# EE194_PCB.net
KiCad netlist of a schematic drawn in Altium Designer
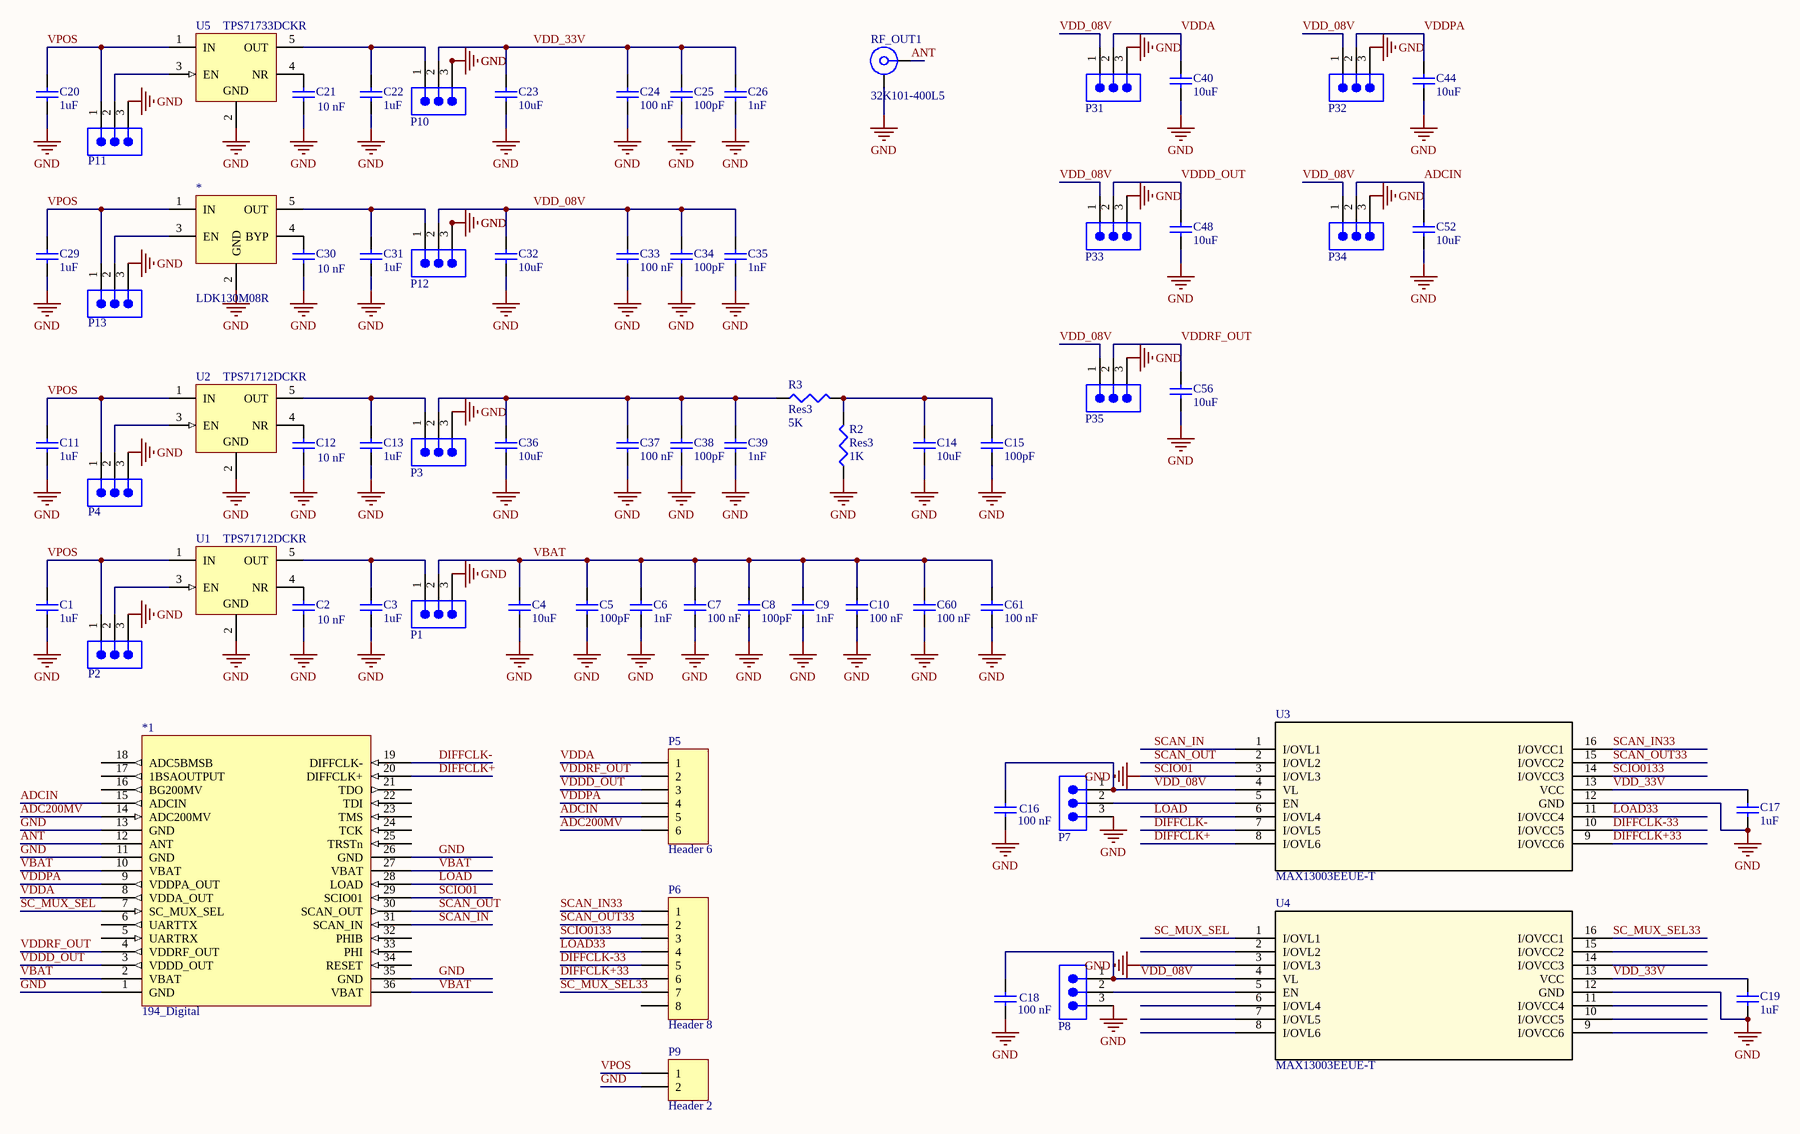
[diagram p0: EE194_PCB.SchDoc]

(export (version "E")
  (design (tool "Eeschema 10.0.6"))
  (components
    (comp (ref "*")
      (value "LDK130M08R")
      (footprint "SOT95P290X145-5N")
      (description "300 mA low quiescent current very low noise LDO (800mV)")
      (libsource (lib "EE194_PCB") (part "LDK130M08R"))
    )
    (comp (ref "*1")
      (value "194_Digital")
      (footprint "EE194_Analog_Chip")
      (libsource (lib "EE194_PCB") (part "194_Digital"))
    )
    (comp (ref "C1")
      (value "1uF")
      (footprint "CAPC0402(1005)60_M")
      (description "CAP 1uF 16V ±10% 0402 (1005 Metric) Thickness 0.6mm SMD")
      (fields (field (name "TOLERANCE") "Â±10%") (field (name "Comment") "CAP 1uF 16V 0402(1005)"))
      (libsource (lib "Altium Content Vault") (part "CAP"))
    )
    (comp (ref "C2")
      (value "GRM155R71H103KA88D")
      (footprint "CAPC1005X55X25LL05T10")
      (description "Chip Capacitor, 10 nF, +/- 10%, 50 V, -55 to 125 degC, 0402 (1005 Metric), RoHS, Tape and Reel")
      (fields
        (field (name "CAPACITANCE") "10 nF")
        (field (name "TOLERANCE") "10%")
        (field (name "MANUFACTURER") "Basic Passives")
      )
      (libsource (lib "Altium Content Vault") (part "CAP-NP-2"))
    )
    (comp (ref "C3")
      (value "1uF")
      (footprint "CAPC0402(1005)60_M")
      (description "CAP 1uF 16V ±10% 0402 (1005 Metric) Thickness 0.6mm SMD")
      (fields (field (name "TOLERANCE") "Â±10%") (field (name "Comment") "CAP 1uF 16V 0402(1005)"))
      (libsource (lib "Altium Content Vault") (part "CAP"))
    )
    (comp (ref "C4")
      (value "10uF")
      (footprint "CAPC0805(2012)145_N")
      (description "CAP 10uF 25V ±10% 0805 (2012 Metric) Thickness 1.45mm SMD")
      (fields (field (name "TOLERANCE") "Â±10%") (field (name "Comment") "CAP 10uF 25V 0805(2012)"))
      (libsource (lib "Altium Content Vault") (part "CAP"))
    )
    (comp (ref "C5")
      (value "100pF")
      (footprint "CAPC0402(1005)60_L")
      (description "CAP 100pF 16V ±1% 0402 (1005 Metric) Thickness 0.6mm SMD")
      (fields (field (name "TOLERANCE") "Â±1%") (field (name "Comment") "CAP 100pF 16V 0402(1005)"))
      (libsource (lib "Altium Content Vault") (part "CAP"))
    )
    (comp (ref "C6")
      (value "1nF")
      (footprint "CAPC0402(1005)60_L")
      (description "CAP 1nF 16V ±1% 0402 (1005 Metric) Thickness 0.6mm SMD")
      (fields (field (name "TOLERANCE") "Â±1%") (field (name "Comment") "CAP 1nF 16V 0402(1005)"))
      (libsource (lib "Altium Content Vault") (part "CAP"))
    )
    (comp (ref "C7")
      (value "0402ZD104KAT2A")
      (footprint "CAPC1005X56X25LL10T15")
      (description "Chip Capacitor, 0.1 uF, +/- 10%, 10 V, -55 to 85 degC, 0402 (1005 Metric), RoHS, Tape and Reel")
      (fields (field (name "CAPACITANCE") "100 nF") (field (name "TOLERANCE") "10%"))
      (libsource (lib "Altium Content Vault") (part "CAP-NP-2"))
    )
    (comp (ref "C8")
      (value "100pF")
      (footprint "CAPC0402(1005)60_L")
      (description "CAP 100pF 16V ±1% 0402 (1005 Metric) Thickness 0.6mm SMD")
      (fields (field (name "TOLERANCE") "Â±1%") (field (name "Comment") "CAP 100pF 16V 0402(1005)"))
      (libsource (lib "Altium Content Vault") (part "CAP"))
    )
    (comp (ref "C9")
      (value "1nF")
      (footprint "CAPC0402(1005)60_L")
      (description "CAP 1nF 16V ±1% 0402 (1005 Metric) Thickness 0.6mm SMD")
      (fields (field (name "TOLERANCE") "Â±1%") (field (name "Comment") "CAP 1nF 16V 0402(1005)"))
      (libsource (lib "Altium Content Vault") (part "CAP"))
    )
    (comp (ref "C10")
      (value "0402ZD104KAT2A")
      (footprint "CAPC1005X56X25LL10T15")
      (description "Chip Capacitor, 0.1 uF, +/- 10%, 10 V, -55 to 85 degC, 0402 (1005 Metric), RoHS, Tape and Reel")
      (fields (field (name "CAPACITANCE") "100 nF") (field (name "TOLERANCE") "10%"))
      (libsource (lib "Altium Content Vault") (part "CAP-NP-2"))
    )
    (comp (ref "C11")
      (value "1uF")
      (footprint "CAPC0402(1005)60_M")
      (description "CAP 1uF 16V ±10% 0402 (1005 Metric) Thickness 0.6mm SMD")
      (fields (field (name "TOLERANCE") "Â±10%") (field (name "Comment") "CAP 1uF 16V 0402(1005)"))
      (libsource (lib "Altium Content Vault") (part "CAP"))
    )
    (comp (ref "C12")
      (value "GRM155R71H103KA88D")
      (footprint "CAPC1005X55X25LL05T10")
      (description "Chip Capacitor, 10 nF, +/- 10%, 50 V, -55 to 125 degC, 0402 (1005 Metric), RoHS, Tape and Reel")
      (fields
        (field (name "CAPACITANCE") "10 nF")
        (field (name "TOLERANCE") "10%")
        (field (name "MANUFACTURER") "Basic Passives")
      )
      (libsource (lib "Altium Content Vault") (part "CAP-NP-2"))
    )
    (comp (ref "C13")
      (value "1uF")
      (footprint "CAPC0402(1005)60_M")
      (description "CAP 1uF 16V ±10% 0402 (1005 Metric) Thickness 0.6mm SMD")
      (fields (field (name "TOLERANCE") "Â±10%") (field (name "Comment") "CAP 1uF 16V 0402(1005)"))
      (libsource (lib "Altium Content Vault") (part "CAP"))
    )
    (comp (ref "C14")
      (value "10uF")
      (footprint "CAPC0805(2012)145_N")
      (description "CAP 10uF 25V ±10% 0805 (2012 Metric) Thickness 1.45mm SMD")
      (fields (field (name "TOLERANCE") "Â±10%") (field (name "Comment") "CAP 10uF 25V 0805(2012)"))
      (libsource (lib "Altium Content Vault") (part "CAP"))
    )
    (comp (ref "C15")
      (value "100pF")
      (footprint "CAPC0402(1005)60_L")
      (description "CAP 100pF 16V ±1% 0402 (1005 Metric) Thickness 0.6mm SMD")
      (fields (field (name "TOLERANCE") "Â±1%") (field (name "Comment") "CAP 100pF 16V 0402(1005)"))
      (libsource (lib "Altium Content Vault") (part "CAP"))
    )
    (comp (ref "C16")
      (value "0402ZD104KAT2A")
      (footprint "CAPC1005X56X25LL10T15")
      (description "Chip Capacitor, 0.1 uF, +/- 10%, 10 V, -55 to 85 degC, 0402 (1005 Metric), RoHS, Tape and Reel")
      (fields (field (name "CAPACITANCE") "100 nF") (field (name "TOLERANCE") "10%"))
      (libsource (lib "Altium Content Vault") (part "CAP-NP-2"))
    )
    (comp (ref "C17")
      (value "1uF")
      (footprint "CAPC0402(1005)60_M")
      (description "CAP 1uF 16V ±10% 0402 (1005 Metric) Thickness 0.6mm SMD")
      (fields (field (name "TOLERANCE") "Â±10%") (field (name "Comment") "CAP 1uF 16V 0402(1005)"))
      (libsource (lib "Altium Content Vault") (part "CAP"))
    )
    (comp (ref "C18")
      (value "0402ZD104KAT2A")
      (footprint "CAPC1005X56X25LL10T15")
      (description "Chip Capacitor, 0.1 uF, +/- 10%, 10 V, -55 to 85 degC, 0402 (1005 Metric), RoHS, Tape and Reel")
      (fields (field (name "CAPACITANCE") "100 nF") (field (name "TOLERANCE") "10%"))
      (libsource (lib "Altium Content Vault") (part "CAP-NP-2"))
    )
    (comp (ref "C19")
      (value "1uF")
      (footprint "CAPC0402(1005)60_M")
      (description "CAP 1uF 16V ±10% 0402 (1005 Metric) Thickness 0.6mm SMD")
      (fields (field (name "TOLERANCE") "Â±10%") (field (name "Comment") "CAP 1uF 16V 0402(1005)"))
      (libsource (lib "Altium Content Vault") (part "CAP"))
    )
    (comp (ref "C20")
      (value "1uF")
      (footprint "CAPC0402(1005)60_M")
      (description "CAP 1uF 16V ±10% 0402 (1005 Metric) Thickness 0.6mm SMD")
      (fields (field (name "TOLERANCE") "Â±10%") (field (name "Comment") "CAP 1uF 16V 0402(1005)"))
      (libsource (lib "Altium Content Vault") (part "CAP"))
    )
    (comp (ref "C21")
      (value "GRM155R71H103KA88D")
      (footprint "CAPC1005X55X25LL05T10")
      (description "Chip Capacitor, 10 nF, +/- 10%, 50 V, -55 to 125 degC, 0402 (1005 Metric), RoHS, Tape and Reel")
      (fields
        (field (name "CAPACITANCE") "10 nF")
        (field (name "TOLERANCE") "10%")
        (field (name "MANUFACTURER") "Basic Passives")
      )
      (libsource (lib "Altium Content Vault") (part "CAP-NP-2"))
    )
    (comp (ref "C22")
      (value "1uF")
      (footprint "CAPC0402(1005)60_M")
      (description "CAP 1uF 16V ±10% 0402 (1005 Metric) Thickness 0.6mm SMD")
      (fields (field (name "TOLERANCE") "Â±10%") (field (name "Comment") "CAP 1uF 16V 0402(1005)"))
      (libsource (lib "Altium Content Vault") (part "CAP"))
    )
    (comp (ref "C23")
      (value "10uF")
      (footprint "CAPC0805(2012)145_N")
      (description "CAP 10uF 25V ±10% 0805 (2012 Metric) Thickness 1.45mm SMD")
      (fields (field (name "TOLERANCE") "Â±10%") (field (name "Comment") "CAP 10uF 25V 0805(2012)"))
      (libsource (lib "Altium Content Vault") (part "CAP"))
    )
    (comp (ref "C24")
      (value "0402ZD104KAT2A")
      (footprint "CAPC1005X56X25LL10T15")
      (description "Chip Capacitor, 0.1 uF, +/- 10%, 10 V, -55 to 85 degC, 0402 (1005 Metric), RoHS, Tape and Reel")
      (fields (field (name "CAPACITANCE") "100 nF") (field (name "TOLERANCE") "10%"))
      (libsource (lib "Altium Content Vault") (part "CAP-NP-2"))
    )
    (comp (ref "C25")
      (value "100pF")
      (footprint "CAPC0402(1005)60_L")
      (description "CAP 100pF 16V ±1% 0402 (1005 Metric) Thickness 0.6mm SMD")
      (fields (field (name "TOLERANCE") "Â±1%") (field (name "Comment") "CAP 100pF 16V 0402(1005)"))
      (libsource (lib "Altium Content Vault") (part "CAP"))
    )
    (comp (ref "C26")
      (value "1nF")
      (footprint "CAPC0402(1005)60_L")
      (description "CAP 1nF 16V ±1% 0402 (1005 Metric) Thickness 0.6mm SMD")
      (fields (field (name "TOLERANCE") "Â±1%") (field (name "Comment") "CAP 1nF 16V 0402(1005)"))
      (libsource (lib "Altium Content Vault") (part "CAP"))
    )
    (comp (ref "C29")
      (value "1uF")
      (footprint "CAPC0402(1005)60_M")
      (description "CAP 1uF 16V ±10% 0402 (1005 Metric) Thickness 0.6mm SMD")
      (fields (field (name "TOLERANCE") "Â±10%") (field (name "Comment") "CAP 1uF 16V 0402(1005)"))
      (libsource (lib "Altium Content Vault") (part "CAP"))
    )
    (comp (ref "C30")
      (value "GRM155R71H103KA88D")
      (footprint "CAPC1005X55X25LL05T10")
      (description "Chip Capacitor, 10 nF, +/- 10%, 50 V, -55 to 125 degC, 0402 (1005 Metric), RoHS, Tape and Reel")
      (fields
        (field (name "CAPACITANCE") "10 nF")
        (field (name "TOLERANCE") "10%")
        (field (name "MANUFACTURER") "Basic Passives")
      )
      (libsource (lib "Altium Content Vault") (part "CAP-NP-2"))
    )
    (comp (ref "C31")
      (value "1uF")
      (footprint "CAPC0402(1005)60_M")
      (description "CAP 1uF 16V ±10% 0402 (1005 Metric) Thickness 0.6mm SMD")
      (fields (field (name "TOLERANCE") "Â±10%") (field (name "Comment") "CAP 1uF 16V 0402(1005)"))
      (libsource (lib "Altium Content Vault") (part "CAP"))
    )
    (comp (ref "C32")
      (value "10uF")
      (footprint "CAPC0805(2012)145_N")
      (description "CAP 10uF 25V ±10% 0805 (2012 Metric) Thickness 1.45mm SMD")
      (fields (field (name "TOLERANCE") "Â±10%") (field (name "Comment") "CAP 10uF 25V 0805(2012)"))
      (libsource (lib "Altium Content Vault") (part "CAP"))
    )
    (comp (ref "C33")
      (value "0402ZD104KAT2A")
      (footprint "CAPC1005X56X25LL10T15")
      (description "Chip Capacitor, 0.1 uF, +/- 10%, 10 V, -55 to 85 degC, 0402 (1005 Metric), RoHS, Tape and Reel")
      (fields (field (name "CAPACITANCE") "100 nF") (field (name "TOLERANCE") "10%"))
      (libsource (lib "Altium Content Vault") (part "CAP-NP-2"))
    )
    (comp (ref "C34")
      (value "100pF")
      (footprint "CAPC0402(1005)60_L")
      (description "CAP 100pF 16V ±1% 0402 (1005 Metric) Thickness 0.6mm SMD")
      (fields (field (name "TOLERANCE") "Â±1%") (field (name "Comment") "CAP 100pF 16V 0402(1005)"))
      (libsource (lib "Altium Content Vault") (part "CAP"))
    )
    (comp (ref "C35")
      (value "1nF")
      (footprint "CAPC0402(1005)60_L")
      (description "CAP 1nF 16V ±1% 0402 (1005 Metric) Thickness 0.6mm SMD")
      (fields (field (name "TOLERANCE") "Â±1%") (field (name "Comment") "CAP 1nF 16V 0402(1005)"))
      (libsource (lib "Altium Content Vault") (part "CAP"))
    )
    (comp (ref "C36")
      (value "10uF")
      (footprint "CAPC0805(2012)145_N")
      (description "CAP 10uF 25V ±10% 0805 (2012 Metric) Thickness 1.45mm SMD")
      (fields (field (name "TOLERANCE") "Â±10%") (field (name "Comment") "CAP 10uF 25V 0805(2012)"))
      (libsource (lib "Altium Content Vault") (part "CAP"))
    )
    (comp (ref "C37")
      (value "0402ZD104KAT2A")
      (footprint "CAPC1005X56X25LL10T15")
      (description "Chip Capacitor, 0.1 uF, +/- 10%, 10 V, -55 to 85 degC, 0402 (1005 Metric), RoHS, Tape and Reel")
      (fields (field (name "CAPACITANCE") "100 nF") (field (name "TOLERANCE") "10%"))
      (libsource (lib "Altium Content Vault") (part "CAP-NP-2"))
    )
    (comp (ref "C38")
      (value "100pF")
      (footprint "CAPC0402(1005)60_L")
      (description "CAP 100pF 16V ±1% 0402 (1005 Metric) Thickness 0.6mm SMD")
      (fields (field (name "TOLERANCE") "Â±1%") (field (name "Comment") "CAP 100pF 16V 0402(1005)"))
      (libsource (lib "Altium Content Vault") (part "CAP"))
    )
    (comp (ref "C39")
      (value "1nF")
      (footprint "CAPC0402(1005)60_L")
      (description "CAP 1nF 16V ±1% 0402 (1005 Metric) Thickness 0.6mm SMD")
      (fields (field (name "TOLERANCE") "Â±1%") (field (name "Comment") "CAP 1nF 16V 0402(1005)"))
      (libsource (lib "Altium Content Vault") (part "CAP"))
    )
    (comp (ref "C40")
      (value "10uF")
      (footprint "CAPC0805(2012)145_N")
      (description "CAP 10uF 25V ±10% 0805 (2012 Metric) Thickness 1.45mm SMD")
      (fields (field (name "TOLERANCE") "Â±10%") (field (name "Comment") "CAP 10uF 25V 0805(2012)"))
      (libsource (lib "Altium Content Vault") (part "CAP"))
    )
    (comp (ref "C44")
      (value "10uF")
      (footprint "CAPC0805(2012)145_N")
      (description "CAP 10uF 25V ±10% 0805 (2012 Metric) Thickness 1.45mm SMD")
      (fields (field (name "TOLERANCE") "Â±10%") (field (name "Comment") "CAP 10uF 25V 0805(2012)"))
      (libsource (lib "Altium Content Vault") (part "CAP"))
    )
    (comp (ref "C48")
      (value "10uF")
      (footprint "CAPC0805(2012)145_N")
      (description "CAP 10uF 25V ±10% 0805 (2012 Metric) Thickness 1.45mm SMD")
      (fields (field (name "TOLERANCE") "Â±10%") (field (name "Comment") "CAP 10uF 25V 0805(2012)"))
      (libsource (lib "Altium Content Vault") (part "CAP"))
    )
    (comp (ref "C52")
      (value "10uF")
      (footprint "CAPC0805(2012)145_N")
      (description "CAP 10uF 25V ±10% 0805 (2012 Metric) Thickness 1.45mm SMD")
      (fields (field (name "TOLERANCE") "Â±10%") (field (name "Comment") "CAP 10uF 25V 0805(2012)"))
      (libsource (lib "Altium Content Vault") (part "CAP"))
    )
    (comp (ref "C56")
      (value "10uF")
      (footprint "CAPC0805(2012)145_N")
      (description "CAP 10uF 25V ±10% 0805 (2012 Metric) Thickness 1.45mm SMD")
      (fields (field (name "TOLERANCE") "Â±10%") (field (name "Comment") "CAP 10uF 25V 0805(2012)"))
      (libsource (lib "Altium Content Vault") (part "CAP"))
    )
    (comp (ref "C60")
      (value "0402ZD104KAT2A")
      (footprint "CAPC1005X56X25LL10T15")
      (description "Chip Capacitor, 0.1 uF, +/- 10%, 10 V, -55 to 85 degC, 0402 (1005 Metric), RoHS, Tape and Reel")
      (fields (field (name "CAPACITANCE") "100 nF") (field (name "TOLERANCE") "10%"))
      (libsource (lib "EE194_PCB") (part "CAP-NP-2"))
    )
    (comp (ref "C61")
      (value "0402ZD104KAT2A")
      (footprint "CAPC0402(1005)60_L")
      (description "Chip Capacitor, 0.1 uF, +/- 10%, 10 V, -55 to 85 degC, 0402 (1005 Metric), RoHS, Tape and Reel")
      (fields (field (name "CAPACITANCE") "100 nF") (field (name "TOLERANCE") "10%"))
      (libsource (lib "EE194_PCB") (part "CAP-NP-2"))
    )
    (comp (ref "P1")
      (value "TSW-103-07-F-S")
      (footprint "SMTC-TSW-103-07-X-S")
      (description "0.025\" SQ Post Header, Through-hole, Vertical, -55 to 125 degC, 2.54 mm Pitch, 3-Pin, Male, RoHS")
      (fields (field (name "MANUFACTURER") "Samtec"))
      (libsource (lib "Altium Content Vault") (part "SMTC-TSW-103-X-X-S-X"))
    )
    (comp (ref "P2")
      (value "TSW-103-07-F-S")
      (footprint "SMTC-TSW-103-07-X-S")
      (description "0.025\" SQ Post Header, Through-hole, Vertical, -55 to 125 degC, 2.54 mm Pitch, 3-Pin, Male, RoHS")
      (fields (field (name "MANUFACTURER") "Samtec"))
      (libsource (lib "Altium Content Vault") (part "SMTC-TSW-103-X-X-S-X"))
    )
    (comp (ref "P3")
      (value "TSW-103-07-F-S")
      (footprint "SMTC-TSW-103-07-X-S")
      (description "0.025\" SQ Post Header, Through-hole, Vertical, -55 to 125 degC, 2.54 mm Pitch, 3-Pin, Male, RoHS")
      (fields (field (name "MANUFACTURER") "Samtec"))
      (libsource (lib "Altium Content Vault") (part "SMTC-TSW-103-X-X-S-X"))
    )
    (comp (ref "P4")
      (value "TSW-103-07-F-S")
      (footprint "SMTC-TSW-103-07-X-S")
      (description "0.025\" SQ Post Header, Through-hole, Vertical, -55 to 125 degC, 2.54 mm Pitch, 3-Pin, Male, RoHS")
      (fields (field (name "MANUFACTURER") "Samtec"))
      (libsource (lib "Altium Content Vault") (part "SMTC-TSW-103-X-X-S-X"))
    )
    (comp (ref "P5")
      (value "Header 6")
      (footprint "HDR1X6")
      (description "Header, 6-Pin")
      (fields (field (name "PUBLISHER") "Altium Limited"))
      (libsource (lib "Miscellaneous Connectors") (part "Header 6"))
    )
    (comp (ref "P6")
      (value "Header 8")
      (footprint "HDR1X8")
      (description "Header, 8-Pin")
      (fields (field (name "PUBLISHER") "Altium Limited"))
      (libsource (lib "Miscellaneous Connectors") (part "Header 8"))
    )
    (comp (ref "P7")
      (value "TSW-103-07-F-S")
      (footprint "SMTC-TSW-103-07-X-S")
      (description "0.025\" SQ Post Header, Through-hole, Vertical, -55 to 125 degC, 2.54 mm Pitch, 3-Pin, Male, RoHS")
      (fields (field (name "MANUFACTURER") "Samtec"))
      (libsource (lib "Altium Content Vault") (part "SMTC-TSW-103-X-X-S-X"))
    )
    (comp (ref "P8")
      (value "TSW-103-07-F-S")
      (footprint "SMTC-TSW-103-07-X-S")
      (description "0.025\" SQ Post Header, Through-hole, Vertical, -55 to 125 degC, 2.54 mm Pitch, 3-Pin, Male, RoHS")
      (fields (field (name "MANUFACTURER") "Samtec"))
      (libsource (lib "Altium Content Vault") (part "SMTC-TSW-103-X-X-S-X"))
    )
    (comp (ref "P9")
      (value "Header 2")
      (footprint "HDR1X2")
      (description "Header, 2-Pin")
      (fields (field (name "PUBLISHER") "Altium Limited"))
      (libsource (lib "Miscellaneous Connectors") (part "Header 2"))
    )
    (comp (ref "P10")
      (value "TSW-103-07-F-S")
      (footprint "SMTC-TSW-103-07-X-S")
      (description "0.025\" SQ Post Header, Through-hole, Vertical, -55 to 125 degC, 2.54 mm Pitch, 3-Pin, Male, RoHS")
      (fields (field (name "MANUFACTURER") "Samtec"))
      (libsource (lib "Altium Content Vault") (part "SMTC-TSW-103-X-X-S-X"))
    )
    (comp (ref "P11")
      (value "TSW-103-07-F-S")
      (footprint "SMTC-TSW-103-07-X-S")
      (description "0.025\" SQ Post Header, Through-hole, Vertical, -55 to 125 degC, 2.54 mm Pitch, 3-Pin, Male, RoHS")
      (fields (field (name "MANUFACTURER") "Samtec"))
      (libsource (lib "Altium Content Vault") (part "SMTC-TSW-103-X-X-S-X"))
    )
    (comp (ref "P12")
      (value "TSW-103-07-F-S")
      (footprint "SMTC-TSW-103-07-X-S")
      (description "0.025\" SQ Post Header, Through-hole, Vertical, -55 to 125 degC, 2.54 mm Pitch, 3-Pin, Male, RoHS")
      (fields (field (name "MANUFACTURER") "Samtec"))
      (libsource (lib "Altium Content Vault") (part "SMTC-TSW-103-X-X-S-X"))
    )
    (comp (ref "P13")
      (value "TSW-103-07-F-S")
      (footprint "SMTC-TSW-103-07-X-S")
      (description "0.025\" SQ Post Header, Through-hole, Vertical, -55 to 125 degC, 2.54 mm Pitch, 3-Pin, Male, RoHS")
      (fields (field (name "MANUFACTURER") "Samtec"))
      (libsource (lib "Altium Content Vault") (part "SMTC-TSW-103-X-X-S-X"))
    )
    (comp (ref "P31")
      (value "TSW-103-07-F-S")
      (footprint "SMTC-TSW-103-07-X-S")
      (description "0.025\" SQ Post Header, Through-hole, Vertical, -55 to 125 degC, 2.54 mm Pitch, 3-Pin, Male, RoHS")
      (fields (field (name "MANUFACTURER") "Samtec"))
      (libsource (lib "Altium Content Vault") (part "SMTC-TSW-103-X-X-S-X"))
    )
    (comp (ref "P32")
      (value "TSW-103-07-F-S")
      (footprint "SMTC-TSW-103-07-X-S")
      (description "0.025\" SQ Post Header, Through-hole, Vertical, -55 to 125 degC, 2.54 mm Pitch, 3-Pin, Male, RoHS")
      (fields (field (name "MANUFACTURER") "Samtec"))
      (libsource (lib "Altium Content Vault") (part "SMTC-TSW-103-X-X-S-X"))
    )
    (comp (ref "P33")
      (value "TSW-103-07-F-S")
      (footprint "SMTC-TSW-103-07-X-S")
      (description "0.025\" SQ Post Header, Through-hole, Vertical, -55 to 125 degC, 2.54 mm Pitch, 3-Pin, Male, RoHS")
      (fields (field (name "MANUFACTURER") "Samtec"))
      (libsource (lib "Altium Content Vault") (part "SMTC-TSW-103-X-X-S-X"))
    )
    (comp (ref "P34")
      (value "TSW-103-07-F-S")
      (footprint "SMTC-TSW-103-07-X-S")
      (description "0.025\" SQ Post Header, Through-hole, Vertical, -55 to 125 degC, 2.54 mm Pitch, 3-Pin, Male, RoHS")
      (fields (field (name "MANUFACTURER") "Samtec"))
      (libsource (lib "Altium Content Vault") (part "SMTC-TSW-103-X-X-S-X"))
    )
    (comp (ref "P35")
      (value "TSW-103-07-F-S")
      (footprint "SMTC-TSW-103-07-X-S")
      (description "0.025\" SQ Post Header, Through-hole, Vertical, -55 to 125 degC, 2.54 mm Pitch, 3-Pin, Male, RoHS")
      (fields (field (name "MANUFACTURER") "Samtec"))
      (libsource (lib "Altium Content Vault") (part "SMTC-TSW-103-X-X-S-X"))
    )
    (comp (ref "R2")
      (value "Res3")
      (footprint "J1-0603")
      (description "Resistor")
      (fields (field (name "ALTIUM_VALUE") "1K") (field (name "PUBLISHER") "Altium Limited"))
      (libsource (lib "Miscellaneous Devices") (part "Res3"))
    )
    (comp (ref "R3")
      (value "Res3")
      (footprint "J1-0603")
      (description "Resistor")
      (fields (field (name "ALTIUM_VALUE") "5K") (field (name "PUBLISHER") "Altium Limited"))
      (libsource (lib "Miscellaneous Devices") (part "Res3"))
    )
    (comp (ref "RF_OUT1")
      (value "32K101-400L5")
      (footprint "ROS-32K101-400L5_V")
      (description "SMA Straight Jack, Up to 18 GHz, -55 to 155 degC")
      (fields (field (name "MANUFACTURER") "Rosenberger"))
      (libsource (lib "Altium Content Vault") (part "ROS-CN-1F-RF1"))
    )
    (comp (ref "U1")
      (value "TPS71712DCKR")
      (footprint "DCK0005A_L")
      (fields (field (name "MANUFACTURER") "Texas Instruments"))
      (libsource (lib "Altium Content Vault") (part "TI-TPS79NXX-YYSOT5"))
    )
    (comp (ref "U2")
      (value "TPS71712DCKR")
      (footprint "DCK0005A_L")
      (fields (field (name "MANUFACTURER") "Texas Instruments"))
      (libsource (lib "Altium Content Vault") (part "TI-TPS79NXX-YYSOT5"))
    )
    (comp (ref "U3")
      (value "MAX13003EEUE-T")
      (footprint "21-0066J_16")
      (description "Imported")
      (libsource (lib "MAX13003") (part "MAX13003EEUE-T"))
    )
    (comp (ref "U4")
      (value "MAX13003EEUE-T")
      (footprint "21-0066J_16")
      (description "Imported")
      (libsource (lib "MAX13003") (part "MAX13003EEUE-T"))
    )
    (comp (ref "U5")
      (value "TPS71733DCKR")
      (footprint "DCK0005A_L")
      (fields (field (name "PARTNUMBER") "TPS71712DCKR") (field (name "MANUFACTURER") "Texas Instruments"))
      (libsource (lib "Altium Content Vault") (part "TI-TPS79NXX-YYSOT5"))
    )
  )
  (nets
    (net (code "1") (name "/ADC200MV") (class "Default")
      (node (ref "*1") (pin "14") (pinfunction "ADC200MV_14") (pintype "input"))
      (node (ref "P5") (pin "6") (pinfunction "6_6") (pintype "passive"))
    )
    (net (code "2") (name "/ADCIN") (class "Default")
      (node (ref "*1") (pin "15") (pinfunction "ADCIN_15") (pintype "output"))
      (node (ref "C52") (pin "2") (pinfunction "2_2") (pintype "passive"))
      (node (ref "P34") (pin "2") (pinfunction "2_2") (pintype "passive"))
      (node (ref "P5") (pin "5") (pinfunction "5_5") (pintype "passive"))
    )
    (net (code "3") (name "/ANT") (class "Default")
      (node (ref "*1") (pin "12") (pinfunction "ANT_12") (pintype "passive"))
      (node (ref "RF_OUT1") (pin "1") (pinfunction "1_1") (pintype "passive"))
    )
    (net (code "4") (name "/DIFFCLK+") (class "Default")
      (node (ref "*1") (pin "20") (pinfunction "DIFFCLK+_20") (pintype "input"))
      (node (ref "U3") (pin "8") (pinfunction "I/OVL6_8") (pintype "passive"))
    )
    (net (code "5") (name "/DIFFCLK+33") (class "Default")
      (node (ref "P6") (pin "6") (pinfunction "6_6") (pintype "passive"))
      (node (ref "U3") (pin "9") (pinfunction "I/OVCC6_9") (pintype "passive"))
    )
    (net (code "6") (name "/DIFFCLK-") (class "Default")
      (node (ref "*1") (pin "19") (pinfunction "DIFFCLK-_19") (pintype "input"))
      (node (ref "U3") (pin "7") (pinfunction "I/OVL5_7") (pintype "passive"))
    )
    (net (code "7") (name "/DIFFCLK-33") (class "Default")
      (node (ref "P6") (pin "5") (pinfunction "5_5") (pintype "passive"))
      (node (ref "U3") (pin "10") (pinfunction "I/OVCC5_10") (pintype "passive"))
    )
    (net (code "8") (name "/LOAD") (class "Default")
      (node (ref "*1") (pin "28") (pinfunction "LOAD_28") (pintype "input"))
      (node (ref "U3") (pin "6") (pinfunction "I/OVL4_6") (pintype "passive"))
    )
    (net (code "9") (name "/LOAD33") (class "Default")
      (node (ref "P6") (pin "4") (pinfunction "4_4") (pintype "passive"))
      (node (ref "U3") (pin "11") (pinfunction "I/OVCC4_11") (pintype "passive"))
    )
    (net (code "10") (name "/SCAN_IN") (class "Default")
      (node (ref "*1") (pin "31") (pinfunction "SCAN_IN_31") (pintype "input"))
      (node (ref "U3") (pin "1") (pinfunction "I/OVL1_1") (pintype "passive"))
    )
    (net (code "11") (name "/SCAN_IN33") (class "Default")
      (node (ref "P6") (pin "1") (pinfunction "1_1") (pintype "passive"))
      (node (ref "U3") (pin "16") (pinfunction "I/OVCC1_16") (pintype "passive"))
    )
    (net (code "12") (name "/SCAN_OUT") (class "Default")
      (node (ref "*1") (pin "30") (pinfunction "SCAN_OUT_30") (pintype "output"))
      (node (ref "U3") (pin "2") (pinfunction "I/OVL2_2") (pintype "passive"))
    )
    (net (code "13") (name "/SCAN_OUT33") (class "Default")
      (node (ref "P6") (pin "2") (pinfunction "2_2") (pintype "passive"))
      (node (ref "U3") (pin "15") (pinfunction "I/OVCC2_15") (pintype "passive"))
    )
    (net (code "14") (name "/SCIO0133") (class "Default")
      (node (ref "P6") (pin "3") (pinfunction "3_3") (pintype "passive"))
      (node (ref "U3") (pin "14") (pinfunction "I/OVCC3_14") (pintype "passive"))
    )
    (net (code "15") (name "/SC_MUX_SEL") (class "Default")
      (node (ref "*1") (pin "7") (pinfunction "SC_MUX_SEL_7") (pintype "input"))
      (node (ref "U4") (pin "1") (pinfunction "I/OVL1_1") (pintype "passive"))
    )
    (net (code "16") (name "/SC_MUX_SEL33") (class "Default")
      (node (ref "P6") (pin "7") (pinfunction "7_7") (pintype "passive"))
      (node (ref "U4") (pin "16") (pinfunction "I/OVCC1_16") (pintype "passive"))
    )
    (net (code "17") (name "/VBAT") (class "Default")
      (node (ref "*1") (pin "10") (pinfunction "VBAT_10") (pintype "power_in"))
      (node (ref "*1") (pin "2") (pinfunction "VBAT_2") (pintype "power_in"))
      (node (ref "*1") (pin "27") (pinfunction "VBAT_27") (pintype "power_in"))
      (node (ref "*1") (pin "36") (pinfunction "VBAT_36") (pintype "power_in"))
      (node (ref "C10") (pin "2") (pinfunction "2_2") (pintype "passive"))
      (node (ref "C4") (pin "2") (pinfunction "2_2") (pintype "passive"))
      (node (ref "C5") (pin "2") (pinfunction "2_2") (pintype "passive"))
      (node (ref "C6") (pin "2") (pinfunction "2_2") (pintype "passive"))
      (node (ref "C60") (pin "2") (pinfunction "2_2") (pintype "passive"))
      (node (ref "C61") (pin "2") (pinfunction "2_2") (pintype "passive"))
      (node (ref "C7") (pin "2") (pinfunction "2_2") (pintype "passive"))
      (node (ref "C8") (pin "2") (pinfunction "2_2") (pintype "passive"))
      (node (ref "C9") (pin "2") (pinfunction "2_2") (pintype "passive"))
      (node (ref "P1") (pin "2") (pinfunction "2_2") (pintype "passive"))
    )
    (net (code "18") (name "/VDDA") (class "Default")
      (node (ref "*1") (pin "8") (pinfunction "VDDA_OUT_8") (pintype "output"))
      (node (ref "C40") (pin "2") (pinfunction "2_2") (pintype "passive"))
      (node (ref "P31") (pin "2") (pinfunction "2_2") (pintype "passive"))
      (node (ref "P5") (pin "1") (pinfunction "1_1") (pintype "passive"))
    )
    (net (code "19") (name "/VDDD_OUT") (class "Default")
      (node (ref "*1") (pin "3") (pinfunction "VDDD_OUT_3") (pintype "output"))
      (node (ref "C48") (pin "2") (pinfunction "2_2") (pintype "passive"))
      (node (ref "P33") (pin "2") (pinfunction "2_2") (pintype "passive"))
      (node (ref "P5") (pin "3") (pinfunction "3_3") (pintype "passive"))
    )
    (net (code "20") (name "/VDDPA") (class "Default")
      (node (ref "*1") (pin "9") (pinfunction "VDDPA_OUT_9") (pintype "output"))
      (node (ref "C44") (pin "2") (pinfunction "2_2") (pintype "passive"))
      (node (ref "P32") (pin "2") (pinfunction "2_2") (pintype "passive"))
      (node (ref "P5") (pin "4") (pinfunction "4_4") (pintype "passive"))
    )
    (net (code "21") (name "/VDDRF_OUT") (class "Default")
      (node (ref "*1") (pin "4") (pinfunction "VDDRF_OUT_4") (pintype "output"))
      (node (ref "C56") (pin "2") (pinfunction "2_2") (pintype "passive"))
      (node (ref "P35") (pin "2") (pinfunction "2_2") (pintype "passive"))
      (node (ref "P5") (pin "2") (pinfunction "2_2") (pintype "passive"))
    )
    (net (code "22") (name "/VDD_08V") (class "Default")
      (node (ref "C16") (pin "2") (pinfunction "2_2") (pintype "passive"))
      (node (ref "C18") (pin "2") (pinfunction "2_2") (pintype "passive"))
      (node (ref "C32") (pin "2") (pinfunction "2_2") (pintype "passive"))
      (node (ref "C33") (pin "2") (pinfunction "2_2") (pintype "passive"))
      (node (ref "C34") (pin "2") (pinfunction "2_2") (pintype "passive"))
      (node (ref "C35") (pin "2") (pinfunction "2_2") (pintype "passive"))
      (node (ref "P12") (pin "2") (pinfunction "2_2") (pintype "passive"))
      (node (ref "P31") (pin "1") (pinfunction "1_1") (pintype "passive"))
      (node (ref "P32") (pin "1") (pinfunction "1_1") (pintype "passive"))
      (node (ref "P33") (pin "1") (pinfunction "1_1") (pintype "passive"))
      (node (ref "P34") (pin "1") (pinfunction "1_1") (pintype "passive"))
      (node (ref "P35") (pin "1") (pinfunction "1_1") (pintype "passive"))
      (node (ref "P7") (pin "1") (pinfunction "1_1") (pintype "passive"))
      (node (ref "P8") (pin "1") (pinfunction "1_1") (pintype "passive"))
      (node (ref "U3") (pin "4") (pinfunction "VL_4") (pintype "power_in"))
      (node (ref "U4") (pin "4") (pinfunction "VL_4") (pintype "power_in"))
    )
    (net (code "23") (name "/VDD_33V") (class "Default")
      (node (ref "C17") (pin "1") (pinfunction "1_1") (pintype "passive"))
      (node (ref "C19") (pin "1") (pinfunction "1_1") (pintype "passive"))
      (node (ref "C23") (pin "2") (pinfunction "2_2") (pintype "passive"))
      (node (ref "C24") (pin "2") (pinfunction "2_2") (pintype "passive"))
      (node (ref "C25") (pin "2") (pinfunction "2_2") (pintype "passive"))
      (node (ref "C26") (pin "2") (pinfunction "2_2") (pintype "passive"))
      (node (ref "P10") (pin "2") (pinfunction "2_2") (pintype "passive"))
      (node (ref "U3") (pin "13") (pinfunction "VCC_13") (pintype "power_in"))
      (node (ref "U4") (pin "13") (pinfunction "VCC_13") (pintype "power_in"))
    )
    (net (code "24") (name "/VPOS") (class "Default")
      (node (ref "*") (pin "1") (pinfunction "IN_1") (pintype "passive"))
      (node (ref "C1") (pin "2") (pinfunction "2_2") (pintype "passive"))
      (node (ref "C11") (pin "2") (pinfunction "2_2") (pintype "passive"))
      (node (ref "C20") (pin "2") (pinfunction "2_2") (pintype "passive"))
      (node (ref "C29") (pin "2") (pinfunction "2_2") (pintype "passive"))
      (node (ref "P11") (pin "1") (pinfunction "1_1") (pintype "passive"))
      (node (ref "P13") (pin "1") (pinfunction "1_1") (pintype "passive"))
      (node (ref "P2") (pin "1") (pinfunction "1_1") (pintype "passive"))
      (node (ref "P4") (pin "1") (pinfunction "1_1") (pintype "passive"))
      (node (ref "P9") (pin "1") (pinfunction "1_1") (pintype "passive"))
      (node (ref "U1") (pin "1") (pinfunction "IN_1") (pintype "power_in"))
      (node (ref "U2") (pin "1") (pinfunction "IN_1") (pintype "power_in"))
      (node (ref "U5") (pin "1") (pinfunction "IN_1") (pintype "power_in"))
    )
    (net (code "25") (name "GND") (class "Default")
      (node (ref "*") (pin "2") (pinfunction "GND_2") (pintype "passive"))
      (node (ref "*1") (pin "1") (pinfunction "GND_1") (pintype "power_in"))
      (node (ref "*1") (pin "11") (pinfunction "GND_11") (pintype "power_in"))
      (node (ref "*1") (pin "13") (pinfunction "GND_13") (pintype "power_in"))
      (node (ref "*1") (pin "26") (pinfunction "GND_26") (pintype "power_in"))
      (node (ref "*1") (pin "29") (pinfunction "SCIO01_29") (pintype "input"))
      (node (ref "*1") (pin "35") (pinfunction "GND_35") (pintype "power_in"))
      (node (ref "C1") (pin "1") (pinfunction "1_1") (pintype "passive"))
      (node (ref "C10") (pin "1") (pinfunction "1_1") (pintype "passive"))
      (node (ref "C11") (pin "1") (pinfunction "1_1") (pintype "passive"))
      (node (ref "C12") (pin "1") (pinfunction "1_1") (pintype "passive"))
      (node (ref "C13") (pin "1") (pinfunction "1_1") (pintype "passive"))
      (node (ref "C14") (pin "1") (pinfunction "1_1") (pintype "passive"))
      (node (ref "C15") (pin "1") (pinfunction "1_1") (pintype "passive"))
      (node (ref "C16") (pin "1") (pinfunction "1_1") (pintype "passive"))
      (node (ref "C17") (pin "2") (pinfunction "2_2") (pintype "passive"))
      (node (ref "C18") (pin "1") (pinfunction "1_1") (pintype "passive"))
      (node (ref "C19") (pin "2") (pinfunction "2_2") (pintype "passive"))
      (node (ref "C2") (pin "1") (pinfunction "1_1") (pintype "passive"))
      (node (ref "C20") (pin "1") (pinfunction "1_1") (pintype "passive"))
      (node (ref "C21") (pin "1") (pinfunction "1_1") (pintype "passive"))
      (node (ref "C22") (pin "1") (pinfunction "1_1") (pintype "passive"))
      (node (ref "C23") (pin "1") (pinfunction "1_1") (pintype "passive"))
      (node (ref "C24") (pin "1") (pinfunction "1_1") (pintype "passive"))
      (node (ref "C25") (pin "1") (pinfunction "1_1") (pintype "passive"))
      (node (ref "C26") (pin "1") (pinfunction "1_1") (pintype "passive"))
      (node (ref "C29") (pin "1") (pinfunction "1_1") (pintype "passive"))
      (node (ref "C3") (pin "1") (pinfunction "1_1") (pintype "passive"))
      (node (ref "C30") (pin "1") (pinfunction "1_1") (pintype "passive"))
      (node (ref "C31") (pin "1") (pinfunction "1_1") (pintype "passive"))
      (node (ref "C32") (pin "1") (pinfunction "1_1") (pintype "passive"))
      (node (ref "C33") (pin "1") (pinfunction "1_1") (pintype "passive"))
      (node (ref "C34") (pin "1") (pinfunction "1_1") (pintype "passive"))
      (node (ref "C35") (pin "1") (pinfunction "1_1") (pintype "passive"))
      (node (ref "C36") (pin "1") (pinfunction "1_1") (pintype "passive"))
      (node (ref "C37") (pin "1") (pinfunction "1_1") (pintype "passive"))
      (node (ref "C38") (pin "1") (pinfunction "1_1") (pintype "passive"))
      (node (ref "C39") (pin "1") (pinfunction "1_1") (pintype "passive"))
      (node (ref "C4") (pin "1") (pinfunction "1_1") (pintype "passive"))
      (node (ref "C40") (pin "1") (pinfunction "1_1") (pintype "passive"))
      (node (ref "C44") (pin "1") (pinfunction "1_1") (pintype "passive"))
      (node (ref "C48") (pin "1") (pinfunction "1_1") (pintype "passive"))
      (node (ref "C5") (pin "1") (pinfunction "1_1") (pintype "passive"))
      (node (ref "C52") (pin "1") (pinfunction "1_1") (pintype "passive"))
      (node (ref "C56") (pin "1") (pinfunction "1_1") (pintype "passive"))
      (node (ref "C6") (pin "1") (pinfunction "1_1") (pintype "passive"))
      (node (ref "C60") (pin "1") (pinfunction "1_1") (pintype "passive"))
      (node (ref "C61") (pin "1") (pinfunction "1_1") (pintype "passive"))
      (node (ref "C7") (pin "1") (pinfunction "1_1") (pintype "passive"))
      (node (ref "C8") (pin "1") (pinfunction "1_1") (pintype "passive"))
      (node (ref "C9") (pin "1") (pinfunction "1_1") (pintype "passive"))
      (node (ref "P1") (pin "3") (pinfunction "3_3") (pintype "passive"))
      (node (ref "P10") (pin "3") (pinfunction "3_3") (pintype "passive"))
      (node (ref "P11") (pin "3") (pinfunction "3_3") (pintype "passive"))
      (node (ref "P12") (pin "3") (pinfunction "3_3") (pintype "passive"))
      (node (ref "P13") (pin "3") (pinfunction "3_3") (pintype "passive"))
      (node (ref "P2") (pin "3") (pinfunction "3_3") (pintype "passive"))
      (node (ref "P3") (pin "3") (pinfunction "3_3") (pintype "passive"))
      (node (ref "P31") (pin "3") (pinfunction "3_3") (pintype "passive"))
      (node (ref "P32") (pin "3") (pinfunction "3_3") (pintype "passive"))
      (node (ref "P33") (pin "3") (pinfunction "3_3") (pintype "passive"))
      (node (ref "P34") (pin "3") (pinfunction "3_3") (pintype "passive"))
      (node (ref "P35") (pin "3") (pinfunction "3_3") (pintype "passive"))
      (node (ref "P4") (pin "3") (pinfunction "3_3") (pintype "passive"))
      (node (ref "P7") (pin "3") (pinfunction "3_3") (pintype "passive"))
      (node (ref "P8") (pin "3") (pinfunction "3_3") (pintype "passive"))
      (node (ref "P9") (pin "2") (pinfunction "2_2") (pintype "passive"))
      (node (ref "R2") (pin "1") (pinfunction "1_1") (pintype "passive"))
      (node (ref "RF_OUT1") (pin "MH") (pinfunction "MH_MH") (pintype "passive"))
      (node (ref "U1") (pin "2") (pinfunction "GND_2") (pintype "power_in"))
      (node (ref "U2") (pin "2") (pinfunction "GND_2") (pintype "power_in"))
      (node (ref "U3") (pin "12") (pinfunction "GND_12") (pintype "power_in"))
      (node (ref "U3") (pin "3") (pinfunction "I/OVL3_3") (pintype "passive"))
      (node (ref "U4") (pin "12") (pinfunction "GND_12") (pintype "power_in"))
      (node (ref "U4") (pin "3") (pinfunction "I/OVL3_3") (pintype "passive"))
      (node (ref "U5") (pin "2") (pinfunction "GND_2") (pintype "power_in"))
    )
    (net (code "26") (name "Net-(*-BYP)") (class "Default")
      (node (ref "*") (pin "4") (pinfunction "BYP_4") (pintype "passive"))
      (node (ref "C30") (pin "2") (pinfunction "2_2") (pintype "passive"))
    )
    (net (code "27") (name "Net-(*-EN)") (class "Default")
      (node (ref "*") (pin "3") (pinfunction "EN_3") (pintype "passive"))
      (node (ref "P13") (pin "2") (pinfunction "2_2") (pintype "passive"))
    )
    (net (code "28") (name "Net-(*-OUT)") (class "Default")
      (node (ref "*") (pin "5") (pinfunction "OUT_5") (pintype "passive"))
      (node (ref "C31") (pin "2") (pinfunction "2_2") (pintype "passive"))
      (node (ref "P12") (pin "1") (pinfunction "1_1") (pintype "passive"))
    )
    (net (code "29") (name "Net-(C14-Pad2)") (class "Default")
      (node (ref "C14") (pin "2") (pinfunction "2_2") (pintype "passive"))
      (node (ref "C15") (pin "2") (pinfunction "2_2") (pintype "passive"))
      (node (ref "R2") (pin "2") (pinfunction "2_2") (pintype "passive"))
      (node (ref "R3") (pin "2") (pinfunction "2_2") (pintype "passive"))
    )
    (net (code "30") (name "Net-(C36-Pad2)") (class "Default")
      (node (ref "C36") (pin "2") (pinfunction "2_2") (pintype "passive"))
      (node (ref "C37") (pin "2") (pinfunction "2_2") (pintype "passive"))
      (node (ref "C38") (pin "2") (pinfunction "2_2") (pintype "passive"))
      (node (ref "C39") (pin "2") (pinfunction "2_2") (pintype "passive"))
      (node (ref "P3") (pin "2") (pinfunction "2_2") (pintype "passive"))
      (node (ref "R3") (pin "1") (pinfunction "1_1") (pintype "passive"))
    )
    (net (code "31") (name "Net-(U1-EN)") (class "Default")
      (node (ref "P2") (pin "2") (pinfunction "2_2") (pintype "passive"))
      (node (ref "U1") (pin "3") (pinfunction "EN_3") (pintype "input"))
    )
    (net (code "32") (name "Net-(U1-NR)") (class "Default")
      (node (ref "C2") (pin "2") (pinfunction "2_2") (pintype "passive"))
      (node (ref "U1") (pin "4") (pinfunction "NR_4") (pintype "passive"))
    )
    (net (code "33") (name "Net-(U1-OUT)") (class "Default")
      (node (ref "C3") (pin "2") (pinfunction "2_2") (pintype "passive"))
      (node (ref "P1") (pin "1") (pinfunction "1_1") (pintype "passive"))
      (node (ref "U1") (pin "5") (pinfunction "OUT_5") (pintype "power_in"))
    )
    (net (code "34") (name "Net-(U2-EN)") (class "Default")
      (node (ref "P4") (pin "2") (pinfunction "2_2") (pintype "passive"))
      (node (ref "U2") (pin "3") (pinfunction "EN_3") (pintype "input"))
    )
    (net (code "35") (name "Net-(U2-NR)") (class "Default")
      (node (ref "C12") (pin "2") (pinfunction "2_2") (pintype "passive"))
      (node (ref "U2") (pin "4") (pinfunction "NR_4") (pintype "passive"))
    )
    (net (code "36") (name "Net-(U2-OUT)") (class "Default")
      (node (ref "C13") (pin "2") (pinfunction "2_2") (pintype "passive"))
      (node (ref "P3") (pin "1") (pinfunction "1_1") (pintype "passive"))
      (node (ref "U2") (pin "5") (pinfunction "OUT_5") (pintype "power_in"))
    )
    (net (code "37") (name "Net-(U3-EN)") (class "Default")
      (node (ref "P7") (pin "2") (pinfunction "2_2") (pintype "passive"))
      (node (ref "U3") (pin "5") (pinfunction "EN_5") (pintype "passive"))
    )
    (net (code "38") (name "Net-(U4-EN)") (class "Default")
      (node (ref "P8") (pin "2") (pinfunction "2_2") (pintype "passive"))
      (node (ref "U4") (pin "5") (pinfunction "EN_5") (pintype "passive"))
    )
    (net (code "39") (name "Net-(U5-EN)") (class "Default")
      (node (ref "P11") (pin "2") (pinfunction "2_2") (pintype "passive"))
      (node (ref "U5") (pin "3") (pinfunction "EN_3") (pintype "input"))
    )
    (net (code "40") (name "Net-(U5-NR)") (class "Default")
      (node (ref "C21") (pin "2") (pinfunction "2_2") (pintype "passive"))
      (node (ref "U5") (pin "4") (pinfunction "NR_4") (pintype "passive"))
    )
    (net (code "41") (name "Net-(U5-OUT)") (class "Default")
      (node (ref "C22") (pin "2") (pinfunction "2_2") (pintype "passive"))
      (node (ref "P10") (pin "1") (pinfunction "1_1") (pintype "passive"))
      (node (ref "U5") (pin "5") (pinfunction "OUT_5") (pintype "power_in"))
    )
    (net (code "42") (name "unconnected-(*1-1BSAOUTPUT-Pad17)") (class "Default")
      (node (ref "*1") (pin "17") (pinfunction "1BSAOUTPUT_17") (pintype "output"))
    )
    (net (code "43") (name "unconnected-(*1-ADC5BMSB-Pad18)") (class "Default")
      (node (ref "*1") (pin "18") (pinfunction "ADC5BMSB_18") (pintype "output"))
    )
    (net (code "44") (name "unconnected-(*1-BG200MV-Pad16)") (class "Default")
      (node (ref "*1") (pin "16") (pinfunction "BG200MV_16") (pintype "output"))
    )
    (net (code "45") (name "unconnected-(*1-PHI-Pad33)") (class "Default")
      (node (ref "*1") (pin "33") (pinfunction "PHI_33") (pintype "input"))
    )
    (net (code "46") (name "unconnected-(*1-PHIB-Pad32)") (class "Default")
      (node (ref "*1") (pin "32") (pinfunction "PHIB_32") (pintype "input"))
    )
    (net (code "47") (name "unconnected-(*1-RESET-Pad34)") (class "Default")
      (node (ref "*1") (pin "34") (pinfunction "RESET_34") (pintype "input"))
    )
    (net (code "48") (name "unconnected-(*1-TCK-Pad24)") (class "Default")
      (node (ref "*1") (pin "24") (pinfunction "TCK_24") (pintype "input"))
    )
    (net (code "49") (name "unconnected-(*1-TDI-Pad22)") (class "Default")
      (node (ref "*1") (pin "22") (pinfunction "TDI_22") (pintype "input"))
    )
    (net (code "50") (name "unconnected-(*1-TDO-Pad21)") (class "Default")
      (node (ref "*1") (pin "21") (pinfunction "TDO_21") (pintype "output"))
    )
    (net (code "51") (name "unconnected-(*1-TMS-Pad23)") (class "Default")
      (node (ref "*1") (pin "23") (pinfunction "TMS_23") (pintype "input"))
    )
    (net (code "52") (name "unconnected-(*1-TRSTn-Pad25)") (class "Default")
      (node (ref "*1") (pin "25") (pinfunction "TRSTn_25") (pintype "input"))
    )
    (net (code "53") (name "unconnected-(*1-UARTRX-Pad5)") (class "Default")
      (node (ref "*1") (pin "5") (pinfunction "UARTRX_5") (pintype "input"))
    )
    (net (code "54") (name "unconnected-(*1-UARTTX-Pad6)") (class "Default")
      (node (ref "*1") (pin "6") (pinfunction "UARTTX_6") (pintype "output"))
    )
    (net (code "55") (name "unconnected-(P6-Pad8)") (class "Default")
      (node (ref "P6") (pin "8") (pinfunction "8_8") (pintype "passive"))
    )
    (net (code "56") (name "unconnected-(U4-I{slash}OVCC2-Pad15)") (class "Default")
      (node (ref "U4") (pin "15") (pinfunction "I/OVCC2_15") (pintype "passive"))
    )
    (net (code "57") (name "unconnected-(U4-I{slash}OVCC3-Pad14)") (class "Default")
      (node (ref "U4") (pin "14") (pinfunction "I/OVCC3_14") (pintype "passive"))
    )
    (net (code "58") (name "unconnected-(U4-I{slash}OVCC4-Pad11)") (class "Default")
      (node (ref "U4") (pin "11") (pinfunction "I/OVCC4_11") (pintype "passive"))
    )
    (net (code "59") (name "unconnected-(U4-I{slash}OVCC5-Pad10)") (class "Default")
      (node (ref "U4") (pin "10") (pinfunction "I/OVCC5_10") (pintype "passive"))
    )
    (net (code "60") (name "unconnected-(U4-I{slash}OVCC6-Pad9)") (class "Default")
      (node (ref "U4") (pin "9") (pinfunction "I/OVCC6_9") (pintype "passive"))
    )
    (net (code "61") (name "unconnected-(U4-I{slash}OVL2-Pad2)") (class "Default")
      (node (ref "U4") (pin "2") (pinfunction "I/OVL2_2") (pintype "passive"))
    )
    (net (code "62") (name "unconnected-(U4-I{slash}OVL4-Pad6)") (class "Default")
      (node (ref "U4") (pin "6") (pinfunction "I/OVL4_6") (pintype "passive"))
    )
    (net (code "63") (name "unconnected-(U4-I{slash}OVL5-Pad7)") (class "Default")
      (node (ref "U4") (pin "7") (pinfunction "I/OVL5_7") (pintype "passive"))
    )
    (net (code "64") (name "unconnected-(U4-I{slash}OVL6-Pad8)") (class "Default")
      (node (ref "U4") (pin "8") (pinfunction "I/OVL6_8") (pintype "passive"))
    )
  )
)
